# SMTRelayControllerDense.net
KiCad netlist of a schematic drawn in EAGLE
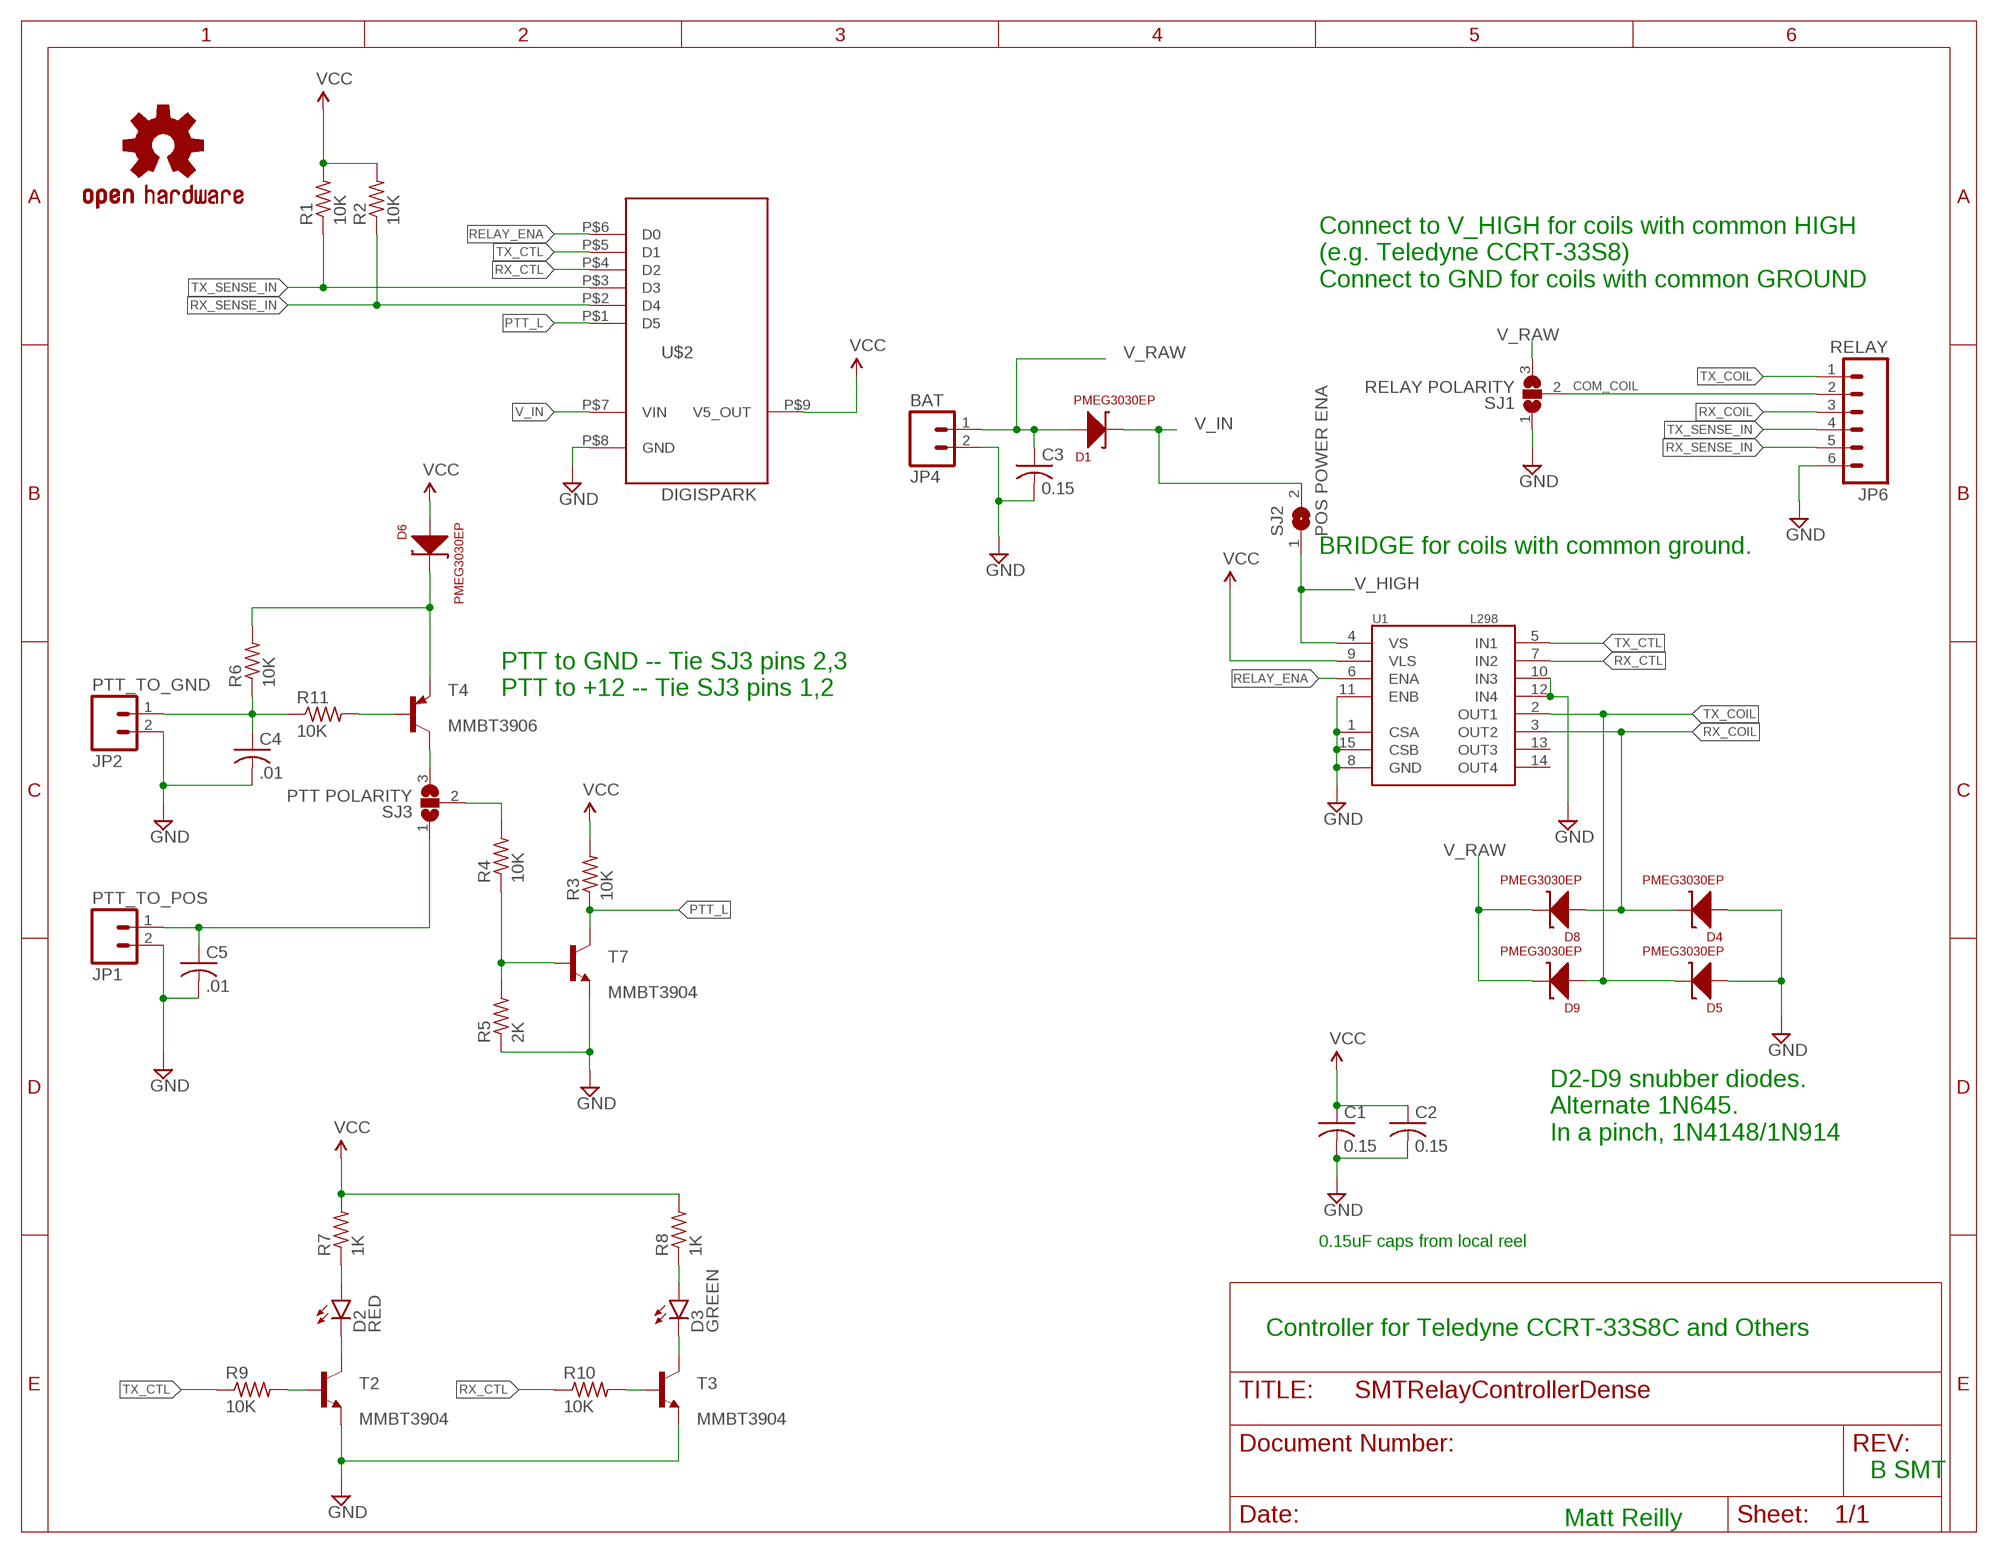
[diagram p0: schematic, sheet 1]

(export (version "E")
  (design (tool "Eeschema 10.0.6"))
  (components
    (comp (ref "C1")
      (value "0.15")
      (footprint "eagle-import:C1206K")
      (libsource (lib "eagle-import") (part "C-USC1206K"))
    )
    (comp (ref "C2")
      (value "0.15")
      (footprint "eagle-import:C1206K")
      (libsource (lib "eagle-import") (part "C-USC1206K"))
    )
    (comp (ref "C3")
      (value "0.15")
      (footprint "eagle-import:C1206K")
      (libsource (lib "eagle-import") (part "C-USC1206K"))
    )
    (comp (ref "C4")
      (value ".01")
      (footprint "eagle-import:C1206K")
      (libsource (lib "eagle-import") (part "C-USC1206K"))
    )
    (comp (ref "C5")
      (value ".01")
      (footprint "eagle-import:C1206K")
      (libsource (lib "eagle-import") (part "C-USC1206K"))
    )
    (comp (ref "D1")
      (value "PMEG3030EP")
      (footprint "eagle-import:SOD128")
      (libsource (lib "eagle-import") (part "PMEG3030EP"))
    )
    (comp (ref "D2")
      (value "RED")
      (footprint "eagle-import:LED-1206")
      (libsource (lib "eagle-import") (part "LED1206"))
    )
    (comp (ref "D3")
      (value "GREEN")
      (footprint "eagle-import:LED-1206")
      (libsource (lib "eagle-import") (part "LED1206"))
    )
    (comp (ref "D4")
      (value "PMEG3030EP")
      (footprint "eagle-import:SOD128")
      (libsource (lib "eagle-import") (part "PMEG3030EP"))
    )
    (comp (ref "D5")
      (value "PMEG3030EP")
      (footprint "eagle-import:SOD128")
      (libsource (lib "eagle-import") (part "PMEG3030EP"))
    )
    (comp (ref "D6")
      (value "PMEG3030EP")
      (footprint "eagle-import:SOD128")
      (libsource (lib "eagle-import") (part "PMEG3030EP"))
    )
    (comp (ref "D8")
      (value "PMEG3030EP")
      (footprint "eagle-import:SOD128")
      (libsource (lib "eagle-import") (part "PMEG3030EP"))
    )
    (comp (ref "D9")
      (value "PMEG3030EP")
      (footprint "eagle-import:SOD128")
      (libsource (lib "eagle-import") (part "PMEG3030EP"))
    )
    (comp (ref "JP1")
      (value "PTT_TO_POS")
      (footprint "eagle-import:SCREWTERMINAL-5MM-2")
      (libsource (lib "eagle-import") (part "M025MM"))
    )
    (comp (ref "JP2")
      (value "PTT_TO_GND")
      (footprint "eagle-import:SCREWTERMINAL-5MM-2")
      (libsource (lib "eagle-import") (part "M025MM"))
    )
    (comp (ref "JP4")
      (value "BAT")
      (footprint "eagle-import:SCREWTERMINAL-5MM-2")
      (libsource (lib "eagle-import") (part "M025MM"))
    )
    (comp (ref "JP6")
      (value "RELAY")
      (footprint "eagle-import:MOLEX-1X6")
      (libsource (lib "eagle-import") (part "M06POLAR"))
    )
    (comp (ref "LOGO2")
      (value "OSHW-LOGOM")
      (footprint "eagle-import:OSHW-LOGO-M")
      (libsource (lib "eagle-import") (part "OSHW-LOGOM"))
    )
    (comp (ref "R1")
      (value "10K")
      (footprint "eagle-import:R1206")
      (libsource (lib "eagle-import") (part "R-US_R1206"))
    )
    (comp (ref "R2")
      (value "10K")
      (footprint "eagle-import:R1206")
      (libsource (lib "eagle-import") (part "R-US_R1206"))
    )
    (comp (ref "R3")
      (value "10K")
      (footprint "eagle-import:R1206")
      (libsource (lib "eagle-import") (part "R-US_R1206"))
    )
    (comp (ref "R4")
      (value "10K")
      (footprint "eagle-import:R1206")
      (libsource (lib "eagle-import") (part "R-US_R1206"))
    )
    (comp (ref "R5")
      (value "2K")
      (footprint "eagle-import:R1206")
      (libsource (lib "eagle-import") (part "R-US_R1206"))
    )
    (comp (ref "R6")
      (value "10K")
      (footprint "eagle-import:R1206")
      (libsource (lib "eagle-import") (part "R-US_R1206"))
    )
    (comp (ref "R7")
      (value "1K")
      (footprint "eagle-import:R1206")
      (libsource (lib "eagle-import") (part "R-US_R1206"))
    )
    (comp (ref "R8")
      (value "1K")
      (footprint "eagle-import:R1206")
      (libsource (lib "eagle-import") (part "R-US_R1206"))
    )
    (comp (ref "R9")
      (value "10K")
      (footprint "eagle-import:R1206")
      (libsource (lib "eagle-import") (part "R-US_R1206"))
    )
    (comp (ref "R10")
      (value "10K")
      (footprint "eagle-import:R1206")
      (libsource (lib "eagle-import") (part "R-US_R1206"))
    )
    (comp (ref "R11")
      (value "10K")
      (footprint "eagle-import:R1206")
      (libsource (lib "eagle-import") (part "R-US_R1206"))
    )
    (comp (ref "SJ1")
      (value "RELAY POLARITY")
      (footprint "eagle-import:SJ_2W")
      (libsource (lib "eagle-import") (part "SJ2WW"))
    )
    (comp (ref "SJ2")
      (value "POS POWER ENA")
      (footprint "eagle-import:SJW")
      (libsource (lib "eagle-import") (part "SJW"))
    )
    (comp (ref "SJ3")
      (value "PTT POLARITY")
      (footprint "eagle-import:SJ_2W")
      (libsource (lib "eagle-import") (part "SJ2WW"))
    )
    (comp (ref "T2")
      (value "MMBT3904")
      (footprint "eagle-import:SOT23-BEC")
      (libsource (lib "eagle-import") (part "-NPN-SOT23-BECMMBT3904LT1"))
    )
    (comp (ref "T3")
      (value "MMBT3904")
      (footprint "eagle-import:SOT23-BEC")
      (libsource (lib "eagle-import") (part "-NPN-SOT23-BECMMBT3904LT1"))
    )
    (comp (ref "T4")
      (value "MMBT3906")
      (footprint "eagle-import:SOT23-BEC")
      (libsource (lib "eagle-import") (part "-PNP-SOT23-BECMMBT3906LT1"))
    )
    (comp (ref "T7")
      (value "MMBT3904")
      (footprint "eagle-import:SOT23-BEC")
      (libsource (lib "eagle-import") (part "-NPN-SOT23-BECMMBT3904LT1"))
    )
    (comp (ref "U$2")
      (value "DIGISPARK")
      (footprint "eagle-import:DIGISPARK_FP")
      (libsource (lib "eagle-import") (part "DIGISPARK"))
    )
    (comp (ref "U1")
      (value "L298")
      (footprint "eagle-import:MULTIWATT15")
      (libsource (lib "eagle-import") (part "L298"))
    )
  )
  (nets
    (net (code "1") (name "/COM_COIL") (class "Default")
      (node (ref "JP6") (pin "2") (pinfunction "2_2") (pintype "passive"))
      (node (ref "SJ1") (pin "2") (pinfunction "2_2") (pintype "passive"))
    )
    (net (code "2") (name "/V_HIGH") (class "Default")
      (node (ref "SJ2") (pin "1") (pinfunction "1_1") (pintype "passive"))
      (node (ref "U1") (pin "4") (pinfunction "VS_4") (pintype "bidirectional"))
    )
    (net (code "3") (name "/V_RAW") (class "Default")
      (node (ref "C3") (pin "1") (pinfunction "1_1") (pintype "passive"))
      (node (ref "D1") (pin "P$1") (pinfunction "A_P$1") (pintype "bidirectional"))
      (node (ref "D8") (pin "P$2") (pinfunction "C_P$2") (pintype "bidirectional"))
      (node (ref "D9") (pin "P$2") (pinfunction "C_P$2") (pintype "bidirectional"))
      (node (ref "JP4") (pin "1") (pinfunction "1_1") (pintype "passive"))
      (node (ref "SJ1") (pin "3") (pinfunction "3_3") (pintype "passive"))
    )
    (net (code "4") (name "GND") (class "Default")
      (node (ref "C1") (pin "2") (pinfunction "2_2") (pintype "passive"))
      (node (ref "C2") (pin "2") (pinfunction "2_2") (pintype "passive"))
      (node (ref "C3") (pin "2") (pinfunction "2_2") (pintype "passive"))
      (node (ref "C4") (pin "2") (pinfunction "2_2") (pintype "passive"))
      (node (ref "C5") (pin "2") (pinfunction "2_2") (pintype "passive"))
      (node (ref "D4") (pin "P$1") (pinfunction "A_P$1") (pintype "bidirectional"))
      (node (ref "D5") (pin "P$1") (pinfunction "A_P$1") (pintype "bidirectional"))
      (node (ref "JP1") (pin "2") (pinfunction "2_2") (pintype "passive"))
      (node (ref "JP2") (pin "2") (pinfunction "2_2") (pintype "passive"))
      (node (ref "JP4") (pin "2") (pinfunction "2_2") (pintype "passive"))
      (node (ref "JP6") (pin "6") (pinfunction "6_6") (pintype "passive"))
      (node (ref "R5") (pin "1") (pinfunction "1_1") (pintype "passive"))
      (node (ref "SJ1") (pin "1") (pinfunction "1_1") (pintype "passive"))
      (node (ref "T2") (pin "E") (pinfunction "E_E") (pintype "passive"))
      (node (ref "T3") (pin "E") (pinfunction "E_E") (pintype "passive"))
      (node (ref "T7") (pin "E") (pinfunction "E_E") (pintype "passive"))
      (node (ref "U$2") (pin "P$8") (pinfunction "GND_P$8") (pintype "bidirectional"))
      (node (ref "U1") (pin "1") (pinfunction "CSA_1") (pintype "bidirectional"))
      (node (ref "U1") (pin "10") (pinfunction "IN3_10") (pintype "bidirectional"))
      (node (ref "U1") (pin "11") (pinfunction "ENB_11") (pintype "bidirectional"))
      (node (ref "U1") (pin "12") (pinfunction "IN4_12") (pintype "bidirectional"))
      (node (ref "U1") (pin "15") (pinfunction "CSB_15") (pintype "bidirectional"))
      (node (ref "U1") (pin "8") (pinfunction "GND_8") (pintype "bidirectional"))
    )
    (net (code "5") (name "Net-(C4-Pad1)") (class "Default")
      (node (ref "C4") (pin "1") (pinfunction "1_1") (pintype "passive"))
      (node (ref "JP2") (pin "1") (pinfunction "1_1") (pintype "passive"))
      (node (ref "R11") (pin "1") (pinfunction "1_1") (pintype "passive"))
      (node (ref "R6") (pin "1") (pinfunction "1_1") (pintype "passive"))
    )
    (net (code "6") (name "Net-(C5-Pad1)") (class "Default")
      (node (ref "C5") (pin "1") (pinfunction "1_1") (pintype "passive"))
      (node (ref "JP1") (pin "1") (pinfunction "1_1") (pintype "passive"))
      (node (ref "SJ3") (pin "1") (pinfunction "1_1") (pintype "passive"))
    )
    (net (code "7") (name "Net-(D2-PadA)") (class "Default")
      (node (ref "D2") (pin "A") (pinfunction "A_A") (pintype "passive"))
      (node (ref "R7") (pin "1") (pinfunction "1_1") (pintype "passive"))
    )
    (net (code "8") (name "Net-(D2-PadC)") (class "Default")
      (node (ref "D2") (pin "C") (pinfunction "C_C") (pintype "passive"))
      (node (ref "T2") (pin "C") (pinfunction "C_C") (pintype "passive"))
    )
    (net (code "9") (name "Net-(D3-PadA)") (class "Default")
      (node (ref "D3") (pin "A") (pinfunction "A_A") (pintype "passive"))
      (node (ref "R8") (pin "1") (pinfunction "1_1") (pintype "passive"))
    )
    (net (code "10") (name "Net-(D3-PadC)") (class "Default")
      (node (ref "D3") (pin "C") (pinfunction "C_C") (pintype "passive"))
      (node (ref "T3") (pin "C") (pinfunction "C_C") (pintype "passive"))
    )
    (net (code "11") (name "Net-(D6-C)") (class "Default")
      (node (ref "D6") (pin "P$2") (pinfunction "C_P$2") (pintype "bidirectional"))
      (node (ref "R6") (pin "2") (pinfunction "2_2") (pintype "passive"))
      (node (ref "T4") (pin "E") (pinfunction "E_E") (pintype "passive"))
    )
    (net (code "12") (name "Net-(R4-Pad1)") (class "Default")
      (node (ref "R4") (pin "1") (pinfunction "1_1") (pintype "passive"))
      (node (ref "R5") (pin "2") (pinfunction "2_2") (pintype "passive"))
      (node (ref "T7") (pin "B") (pinfunction "B_B") (pintype "passive"))
    )
    (net (code "13") (name "Net-(R4-Pad2)") (class "Default")
      (node (ref "R4") (pin "2") (pinfunction "2_2") (pintype "passive"))
      (node (ref "SJ3") (pin "2") (pinfunction "2_2") (pintype "passive"))
    )
    (net (code "14") (name "Net-(R9-Pad2)") (class "Default")
      (node (ref "R9") (pin "2") (pinfunction "2_2") (pintype "passive"))
      (node (ref "T2") (pin "B") (pinfunction "B_B") (pintype "passive"))
    )
    (net (code "15") (name "Net-(R10-Pad2)") (class "Default")
      (node (ref "R10") (pin "2") (pinfunction "2_2") (pintype "passive"))
      (node (ref "T3") (pin "B") (pinfunction "B_B") (pintype "passive"))
    )
    (net (code "16") (name "Net-(R11-Pad2)") (class "Default")
      (node (ref "R11") (pin "2") (pinfunction "2_2") (pintype "passive"))
      (node (ref "T4") (pin "B") (pinfunction "B_B") (pintype "passive"))
    )
    (net (code "17") (name "Net-(SJ3-Pad3)") (class "Default")
      (node (ref "SJ3") (pin "3") (pinfunction "3_3") (pintype "passive"))
      (node (ref "T4") (pin "C") (pinfunction "C_C") (pintype "passive"))
    )
    (net (code "18") (name "PTT_L") (class "Default")
      (node (ref "R3") (pin "1") (pinfunction "1_1") (pintype "passive"))
      (node (ref "T7") (pin "C") (pinfunction "C_C") (pintype "passive"))
      (node (ref "U$2") (pin "P$1") (pinfunction "D5_P$1") (pintype "bidirectional"))
    )
    (net (code "19") (name "RELAY_ENA") (class "Default")
      (node (ref "U$2") (pin "P$6") (pinfunction "D0_P$6") (pintype "bidirectional"))
      (node (ref "U1") (pin "6") (pinfunction "ENA_6") (pintype "bidirectional"))
    )
    (net (code "20") (name "RX_COIL") (class "Default")
      (node (ref "D4") (pin "P$2") (pinfunction "C_P$2") (pintype "bidirectional"))
      (node (ref "D8") (pin "P$1") (pinfunction "A_P$1") (pintype "bidirectional"))
      (node (ref "JP6") (pin "3") (pinfunction "3_3") (pintype "passive"))
      (node (ref "U1") (pin "3") (pinfunction "OUT2_3") (pintype "bidirectional"))
    )
    (net (code "21") (name "RX_CTL") (class "Default")
      (node (ref "R10") (pin "1") (pinfunction "1_1") (pintype "passive"))
      (node (ref "U$2") (pin "P$4") (pinfunction "D2_P$4") (pintype "bidirectional"))
      (node (ref "U1") (pin "7") (pinfunction "IN2_7") (pintype "bidirectional"))
    )
    (net (code "22") (name "RX_SENSE_IN") (class "Default")
      (node (ref "JP6") (pin "5") (pinfunction "5_5") (pintype "passive"))
      (node (ref "R2") (pin "1") (pinfunction "1_1") (pintype "passive"))
      (node (ref "U$2") (pin "P$2") (pinfunction "D4_P$2") (pintype "bidirectional"))
    )
    (net (code "23") (name "TX_COIL") (class "Default")
      (node (ref "D5") (pin "P$2") (pinfunction "C_P$2") (pintype "bidirectional"))
      (node (ref "D9") (pin "P$1") (pinfunction "A_P$1") (pintype "bidirectional"))
      (node (ref "JP6") (pin "1") (pinfunction "1_1") (pintype "passive"))
      (node (ref "U1") (pin "2") (pinfunction "OUT1_2") (pintype "bidirectional"))
    )
    (net (code "24") (name "TX_CTL") (class "Default")
      (node (ref "R9") (pin "1") (pinfunction "1_1") (pintype "passive"))
      (node (ref "U$2") (pin "P$5") (pinfunction "D1_P$5") (pintype "bidirectional"))
      (node (ref "U1") (pin "5") (pinfunction "IN1_5") (pintype "bidirectional"))
    )
    (net (code "25") (name "TX_SENSE_IN") (class "Default")
      (node (ref "JP6") (pin "4") (pinfunction "4_4") (pintype "passive"))
      (node (ref "R1") (pin "1") (pinfunction "1_1") (pintype "passive"))
      (node (ref "U$2") (pin "P$3") (pinfunction "D3_P$3") (pintype "bidirectional"))
    )
    (net (code "26") (name "VCC") (class "Default")
      (node (ref "C1") (pin "1") (pinfunction "1_1") (pintype "passive"))
      (node (ref "C2") (pin "1") (pinfunction "1_1") (pintype "passive"))
      (node (ref "D6") (pin "P$1") (pinfunction "A_P$1") (pintype "bidirectional"))
      (node (ref "R1") (pin "2") (pinfunction "2_2") (pintype "passive"))
      (node (ref "R2") (pin "2") (pinfunction "2_2") (pintype "passive"))
      (node (ref "R3") (pin "2") (pinfunction "2_2") (pintype "passive"))
      (node (ref "R7") (pin "2") (pinfunction "2_2") (pintype "passive"))
      (node (ref "R8") (pin "2") (pinfunction "2_2") (pintype "passive"))
      (node (ref "U$2") (pin "P$9") (pinfunction "V5_OUT_P$9") (pintype "bidirectional"))
      (node (ref "U1") (pin "9") (pinfunction "VLS_9") (pintype "bidirectional"))
    )
    (net (code "27") (name "V_IN") (class "Default")
      (node (ref "D1") (pin "P$2") (pinfunction "C_P$2") (pintype "bidirectional"))
      (node (ref "SJ2") (pin "2") (pinfunction "2_2") (pintype "passive"))
      (node (ref "U$2") (pin "P$7") (pinfunction "VIN_P$7") (pintype "bidirectional"))
    )
    (net (code "28") (name "unconnected-(U1-OUT3-Pad13)") (class "Default")
      (node (ref "U1") (pin "13") (pinfunction "OUT3_13") (pintype "bidirectional"))
    )
    (net (code "29") (name "unconnected-(U1-OUT4-Pad14)") (class "Default")
      (node (ref "U1") (pin "14") (pinfunction "OUT4_14") (pintype "bidirectional"))
    )
  )
)
